# micro_board.net
KiCad netlist of a schematic drawn in EAGLE
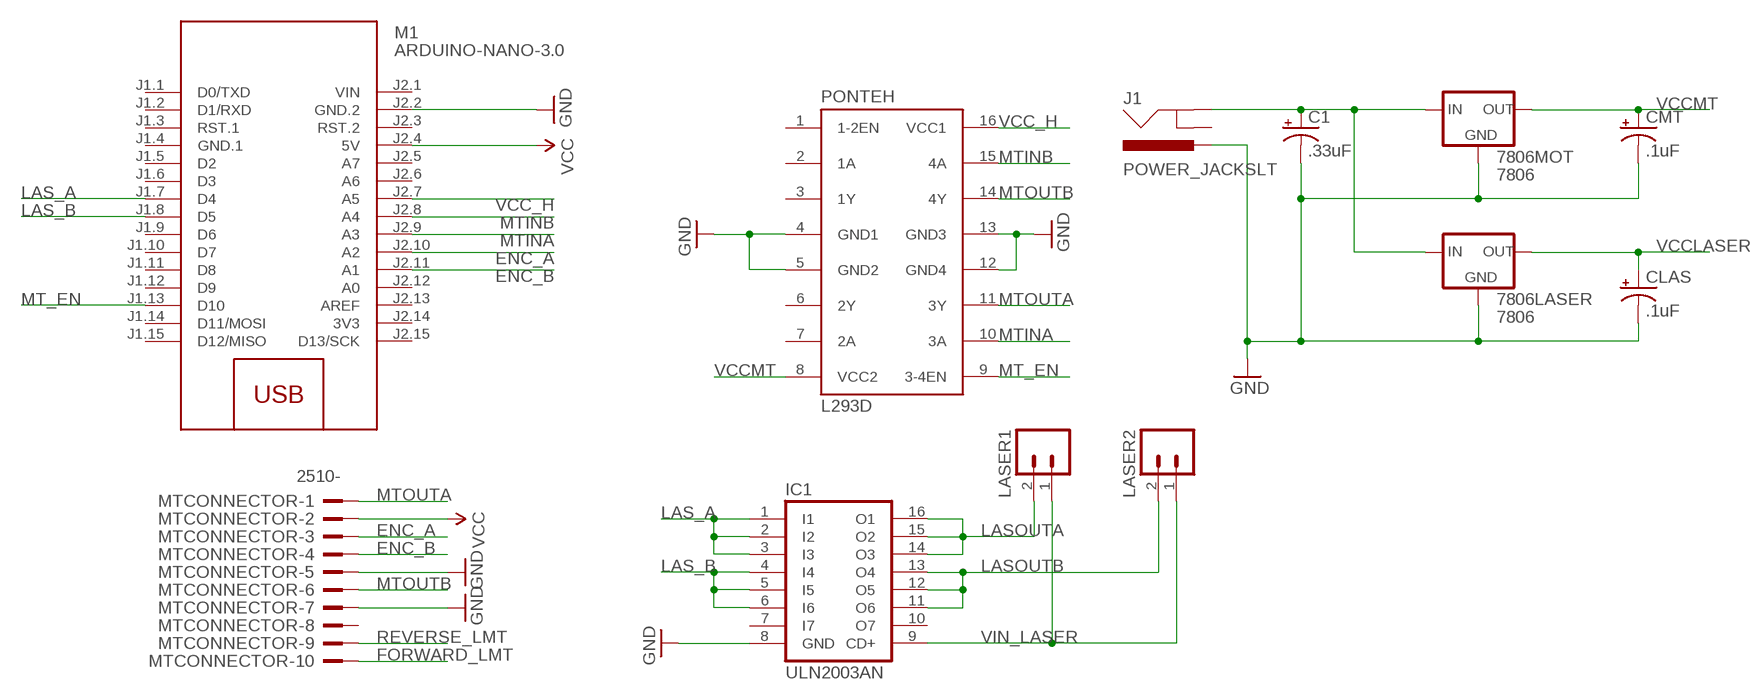
[diagram p0: schematic, sheet 1]

(export (version "E")
  (design (tool "Eeschema 10.0.6"))
  (components
    (comp (ref "7806LASER")
      (value "7806")
      (footprint "eagle-import:TO220-IGO")
      (libsource (lib "eagle-import") (part "V_REG_78XXSINK"))
    )
    (comp (ref "7806MOT")
      (value "7806")
      (footprint "eagle-import:TO220-IGO")
      (libsource (lib "eagle-import") (part "V_REG_78XXSINK"))
    )
    (comp (ref "C1")
      (value ".33uF")
      (footprint "eagle-import:CPOL-RADIAL-100UF-25V")
      (libsource (lib "eagle-import") (part "CAP_POLPTH1"))
    )
    (comp (ref "CLAS")
      (value ".1uF")
      (footprint "eagle-import:CPOL-RADIAL-100UF-25V")
      (libsource (lib "eagle-import") (part "CAP_POLPTH1"))
    )
    (comp (ref "CMT")
      (value ".1uF")
      (footprint "eagle-import:CPOL-RADIAL-100UF-25V")
      (libsource (lib "eagle-import") (part "CAP_POLPTH1"))
    )
    (comp (ref "IC1")
      (value "ULN2003AN")
      (footprint "eagle-import:DIL16")
      (libsource (lib "eagle-import") (part "ULN2003AN"))
    )
    (comp (ref "J1")
      (value "POWER_JACKSLT")
      (footprint "eagle-import:POWER_JACK_SLOT")
      (libsource (lib "eagle-import") (part "POWER_JACKSLT"))
    )
    (comp (ref "LASER1")
      (value "M02POLAR")
      (footprint "eagle-import:MOLEX-1X2")
      (libsource (lib "eagle-import") (part "M02POLAR"))
    )
    (comp (ref "LASER2")
      (value "M02POLAR")
      (footprint "eagle-import:MOLEX-1X2")
      (libsource (lib "eagle-import") (part "M02POLAR"))
    )
    (comp (ref "M1")
      (value "ARDUINO-NANO-3.0")
      (footprint "eagle-import:ARDUINO-NANO-3.0")
      (libsource (lib "eagle-import") (part "ARDUINO-NANO-3.0"))
    )
    (comp (ref "MTCONNECTOR")
      (value "2510-")
      (footprint "eagle-import:PAK100_2500-10")
      (fields (field (name "MF") "3M") (field (name "MPN") "2510-6002UB"))
      (libsource (lib "eagle-import") (part "2510-"))
    )
    (comp (ref "PONTEH")
      (value "L293D")
      (footprint "eagle-import:DIL16")
      (libsource (lib "eagle-import") (part "L293D"))
    )
  )
  (nets
    (net (code "1") (name "/3V3") (class "Default")
      (node (ref "M1") (pin "J2.14") (pinfunction "3V3_J2.14") (pintype "power_in"))
    )
    (net (code "2") (name "/ENC_A") (class "Default")
      (node (ref "M1") (pin "J2.10") (pinfunction "A2_J2.10") (pintype "bidirectional"))
      (node (ref "MTCONNECTOR") (pin "3") (pinfunction "KL_3") (pintype "passive"))
    )
    (net (code "3") (name "/ENC_B") (class "Default")
      (node (ref "M1") (pin "J2.11") (pinfunction "A1_J2.11") (pintype "bidirectional"))
      (node (ref "MTCONNECTOR") (pin "4") (pinfunction "KL_4") (pintype "passive"))
    )
    (net (code "4") (name "/FORWARD_LMT") (class "Default")
      (node (ref "MTCONNECTOR") (pin "10") (pinfunction "KL_10") (pintype "passive"))
    )
    (net (code "5") (name "/GND.1") (class "Default")
      (node (ref "M1") (pin "J1.4") (pinfunction "GND.1_J1.4") (pintype "power_in"))
    )
    (net (code "6") (name "/LASOUTA") (class "Default")
      (node (ref "IC1") (pin "14") (pinfunction "O3_14") (pintype "open_collector"))
      (node (ref "IC1") (pin "15") (pinfunction "O2_15") (pintype "open_collector"))
      (node (ref "IC1") (pin "16") (pinfunction "O1_16") (pintype "open_collector"))
      (node (ref "LASER1") (pin "2") (pinfunction "2_2") (pintype "passive"))
    )
    (net (code "7") (name "/LASOUTB") (class "Default")
      (node (ref "IC1") (pin "11") (pinfunction "O6_11") (pintype "open_collector"))
      (node (ref "IC1") (pin "12") (pinfunction "O5_12") (pintype "open_collector"))
      (node (ref "IC1") (pin "13") (pinfunction "O4_13") (pintype "open_collector"))
      (node (ref "LASER2") (pin "2") (pinfunction "2_2") (pintype "passive"))
    )
    (net (code "8") (name "/LAS_A") (class "Default")
      (node (ref "IC1") (pin "1") (pinfunction "I1_1") (pintype "input"))
      (node (ref "IC1") (pin "2") (pinfunction "I2_2") (pintype "input"))
      (node (ref "IC1") (pin "3") (pinfunction "I3_3") (pintype "input"))
      (node (ref "M1") (pin "J1.7") (pinfunction "D4_J1.7") (pintype "bidirectional"))
    )
    (net (code "9") (name "/LAS_B") (class "Default")
      (node (ref "IC1") (pin "4") (pinfunction "I4_4") (pintype "input"))
      (node (ref "IC1") (pin "5") (pinfunction "I5_5") (pintype "input"))
      (node (ref "IC1") (pin "6") (pinfunction "I6_6") (pintype "input"))
      (node (ref "M1") (pin "J1.8") (pinfunction "D5_J1.8") (pintype "bidirectional"))
    )
    (net (code "10") (name "/MTINA") (class "Default")
      (node (ref "M1") (pin "J2.9") (pinfunction "A3_J2.9") (pintype "bidirectional"))
      (node (ref "PONTEH") (pin "10") (pinfunction "3A_10") (pintype "input"))
    )
    (net (code "11") (name "/MTINB") (class "Default")
      (node (ref "M1") (pin "J2.8") (pinfunction "A4_J2.8") (pintype "bidirectional"))
      (node (ref "PONTEH") (pin "15") (pinfunction "4A_15") (pintype "input"))
    )
    (net (code "12") (name "/MTOUTA") (class "Default")
      (node (ref "MTCONNECTOR") (pin "1") (pinfunction "KL_1") (pintype "passive"))
      (node (ref "PONTEH") (pin "11") (pinfunction "3Y_11") (pintype "output"))
    )
    (net (code "13") (name "/MTOUTB") (class "Default")
      (node (ref "MTCONNECTOR") (pin "6") (pinfunction "KL_6") (pintype "passive"))
      (node (ref "PONTEH") (pin "14") (pinfunction "4Y_14") (pintype "output"))
    )
    (net (code "14") (name "/MT_EN") (class "Default")
      (node (ref "M1") (pin "J1.13") (pinfunction "D10_J1.13") (pintype "bidirectional"))
      (node (ref "PONTEH") (pin "9") (pinfunction "3-4EN_9") (pintype "input"))
    )
    (net (code "15") (name "/REVERSE_LMT") (class "Default")
      (node (ref "MTCONNECTOR") (pin "9") (pinfunction "KL_9") (pintype "passive"))
    )
    (net (code "16") (name "/VCCLASER") (class "Default")
      (node (ref "7806LASER") (pin "OUT") (pinfunction "OUT_OUT") (pintype "passive"))
      (node (ref "CLAS") (pin "1") (pinfunction "+_1") (pintype "passive"))
    )
    (net (code "17") (name "/VCCMT") (class "Default")
      (node (ref "7806MOT") (pin "OUT") (pinfunction "OUT_OUT") (pintype "passive"))
      (node (ref "CMT") (pin "1") (pinfunction "+_1") (pintype "passive"))
      (node (ref "PONTEH") (pin "8") (pinfunction "VCC2_8") (pintype "power_in"))
    )
    (net (code "18") (name "/VCC_H") (class "Default")
      (node (ref "M1") (pin "J2.7") (pinfunction "A5_J2.7") (pintype "bidirectional"))
      (node (ref "PONTEH") (pin "16") (pinfunction "VCC1_16") (pintype "power_in"))
    )
    (net (code "19") (name "/VIN") (class "Default")
      (node (ref "M1") (pin "J2.1") (pinfunction "VIN_J2.1") (pintype "power_in"))
    )
    (net (code "20") (name "/VIN_LASER") (class "Default")
      (node (ref "IC1") (pin "9") (pinfunction "CD+_9") (pintype "passive"))
      (node (ref "LASER1") (pin "1") (pinfunction "1_1") (pintype "passive"))
      (node (ref "LASER2") (pin "1") (pinfunction "1_1") (pintype "passive"))
    )
    (net (code "21") (name "GND") (class "Default")
      (node (ref "7806LASER") (pin "GND") (pinfunction "GND_GND") (pintype "input"))
      (node (ref "7806MOT") (pin "GND") (pinfunction "GND_GND") (pintype "input"))
      (node (ref "C1") (pin "2") (pinfunction "-_2") (pintype "passive"))
      (node (ref "CLAS") (pin "2") (pinfunction "-_2") (pintype "passive"))
      (node (ref "CMT") (pin "2") (pinfunction "-_2") (pintype "passive"))
      (node (ref "IC1") (pin "8") (pinfunction "GND_8") (pintype "power_in"))
      (node (ref "J1") (pin "PWR") (pinfunction "PWR_PWR") (pintype "bidirectional"))
      (node (ref "M1") (pin "J2.2") (pinfunction "GND.2_J2.2") (pintype "power_in"))
      (node (ref "MTCONNECTOR") (pin "5") (pinfunction "KL_5") (pintype "passive"))
      (node (ref "MTCONNECTOR") (pin "7") (pinfunction "KL_7") (pintype "passive"))
      (node (ref "PONTEH") (pin "12") (pinfunction "GND4_12") (pintype "power_in"))
      (node (ref "PONTEH") (pin "13") (pinfunction "GND3_13") (pintype "power_in"))
      (node (ref "PONTEH") (pin "4") (pinfunction "GND1_4") (pintype "power_in"))
      (node (ref "PONTEH") (pin "5") (pinfunction "GND2_5") (pintype "power_in"))
    )
    (net (code "22") (name "Net-(C1-+)") (class "Default")
      (node (ref "7806LASER") (pin "IN") (pinfunction "IN_IN") (pintype "input"))
      (node (ref "7806MOT") (pin "IN") (pinfunction "IN_IN") (pintype "input"))
      (node (ref "C1") (pin "1") (pinfunction "+_1") (pintype "passive"))
      (node (ref "J1") (pin "GND@2") (pinfunction "GND_GND@2") (pintype "bidirectional"))
    )
    (net (code "23") (name "VCC") (class "Default")
      (node (ref "M1") (pin "J2.4") (pinfunction "5V_J2.4") (pintype "power_in"))
      (node (ref "MTCONNECTOR") (pin "2") (pinfunction "KL_2") (pintype "passive"))
    )
    (net (code "24") (name "unconnected-(IC1-I7-Pad7)") (class "Default")
      (node (ref "IC1") (pin "7") (pinfunction "I7_7") (pintype "input"))
    )
    (net (code "25") (name "unconnected-(IC1-O7-Pad10)") (class "Default")
      (node (ref "IC1") (pin "10") (pinfunction "O7_10") (pintype "open_collector"))
    )
    (net (code "26") (name "unconnected-(J1-GNDBREAK-PadGND@1)") (class "Default")
      (node (ref "J1") (pin "GND@1") (pinfunction "GNDBREAK_GND@1") (pintype "bidirectional"))
    )
    (net (code "27") (name "unconnected-(M1-A0-PadJ2.12)") (class "Default")
      (node (ref "M1") (pin "J2.12") (pinfunction "A0_J2.12") (pintype "bidirectional"))
    )
    (net (code "28") (name "unconnected-(M1-A6-PadJ2.6)") (class "Default")
      (node (ref "M1") (pin "J2.6") (pinfunction "A6_J2.6") (pintype "bidirectional"))
    )
    (net (code "29") (name "unconnected-(M1-A7-PadJ2.5)") (class "Default")
      (node (ref "M1") (pin "J2.5") (pinfunction "A7_J2.5") (pintype "bidirectional"))
    )
    (net (code "30") (name "unconnected-(M1-AREF-PadJ2.13)") (class "Default")
      (node (ref "M1") (pin "J2.13") (pinfunction "AREF_J2.13") (pintype "bidirectional"))
    )
    (net (code "31") (name "unconnected-(M1-D0{slash}TXD-PadJ1.1)") (class "Default")
      (node (ref "M1") (pin "J1.1") (pinfunction "D0/TXD_J1.1") (pintype "bidirectional"))
    )
    (net (code "32") (name "unconnected-(M1-D1{slash}RXD-PadJ1.2)") (class "Default")
      (node (ref "M1") (pin "J1.2") (pinfunction "D1/RXD_J1.2") (pintype "bidirectional"))
    )
    (net (code "33") (name "unconnected-(M1-D2-PadJ1.5)") (class "Default")
      (node (ref "M1") (pin "J1.5") (pinfunction "D2_J1.5") (pintype "bidirectional"))
    )
    (net (code "34") (name "unconnected-(M1-D3-PadJ1.6)") (class "Default")
      (node (ref "M1") (pin "J1.6") (pinfunction "D3_J1.6") (pintype "bidirectional"))
    )
    (net (code "35") (name "unconnected-(M1-D6-PadJ1.9)") (class "Default")
      (node (ref "M1") (pin "J1.9") (pinfunction "D6_J1.9") (pintype "bidirectional"))
    )
    (net (code "36") (name "unconnected-(M1-D7-PadJ1.10)") (class "Default")
      (node (ref "M1") (pin "J1.10") (pinfunction "D7_J1.10") (pintype "bidirectional"))
    )
    (net (code "37") (name "unconnected-(M1-D8-PadJ1.11)") (class "Default")
      (node (ref "M1") (pin "J1.11") (pinfunction "D8_J1.11") (pintype "bidirectional"))
    )
    (net (code "38") (name "unconnected-(M1-D9-PadJ1.12)") (class "Default")
      (node (ref "M1") (pin "J1.12") (pinfunction "D9_J1.12") (pintype "bidirectional"))
    )
    (net (code "39") (name "unconnected-(M1-D11{slash}MOSI-PadJ1.14)") (class "Default")
      (node (ref "M1") (pin "J1.14") (pinfunction "D11/MOSI_J1.14") (pintype "bidirectional"))
    )
    (net (code "40") (name "unconnected-(M1-D12{slash}MISO-PadJ1.15)") (class "Default")
      (node (ref "M1") (pin "J1.15") (pinfunction "D12/MISO_J1.15") (pintype "bidirectional"))
    )
    (net (code "41") (name "unconnected-(M1-D13{slash}SCK-PadJ2.15)") (class "Default")
      (node (ref "M1") (pin "J2.15") (pinfunction "D13/SCK_J2.15") (pintype "bidirectional"))
    )
    (net (code "42") (name "unconnected-(M1-RST.1-PadJ1.3)") (class "Default")
      (node (ref "M1") (pin "J1.3") (pinfunction "RST.1_J1.3") (pintype "bidirectional"))
    )
    (net (code "43") (name "unconnected-(M1-RST.2-PadJ2.3)") (class "Default")
      (node (ref "M1") (pin "J2.3") (pinfunction "RST.2_J2.3") (pintype "bidirectional"))
    )
    (net (code "44") (name "unconnected-(MTCONNECTORI-KL-Pad8)") (class "Default")
      (node (ref "MTCONNECTOR") (pin "8") (pinfunction "KL_8") (pintype "passive"))
    )
    (net (code "45") (name "unconnected-(PONTEH-1-2EN-Pad1)") (class "Default")
      (node (ref "PONTEH") (pin "1") (pinfunction "1-2EN_1") (pintype "input"))
    )
    (net (code "46") (name "unconnected-(PONTEH-1A-Pad2)") (class "Default")
      (node (ref "PONTEH") (pin "2") (pinfunction "1A_2") (pintype "input"))
    )
    (net (code "47") (name "unconnected-(PONTEH-1Y-Pad3)") (class "Default")
      (node (ref "PONTEH") (pin "3") (pinfunction "1Y_3") (pintype "output"))
    )
    (net (code "48") (name "unconnected-(PONTEH-2A-Pad7)") (class "Default")
      (node (ref "PONTEH") (pin "7") (pinfunction "2A_7") (pintype "input"))
    )
    (net (code "49") (name "unconnected-(PONTEH-2Y-Pad6)") (class "Default")
      (node (ref "PONTEH") (pin "6") (pinfunction "2Y_6") (pintype "output"))
    )
  )
)
